# 1-Schematic.net
KiCad netlist of a schematic drawn in EasyEDA
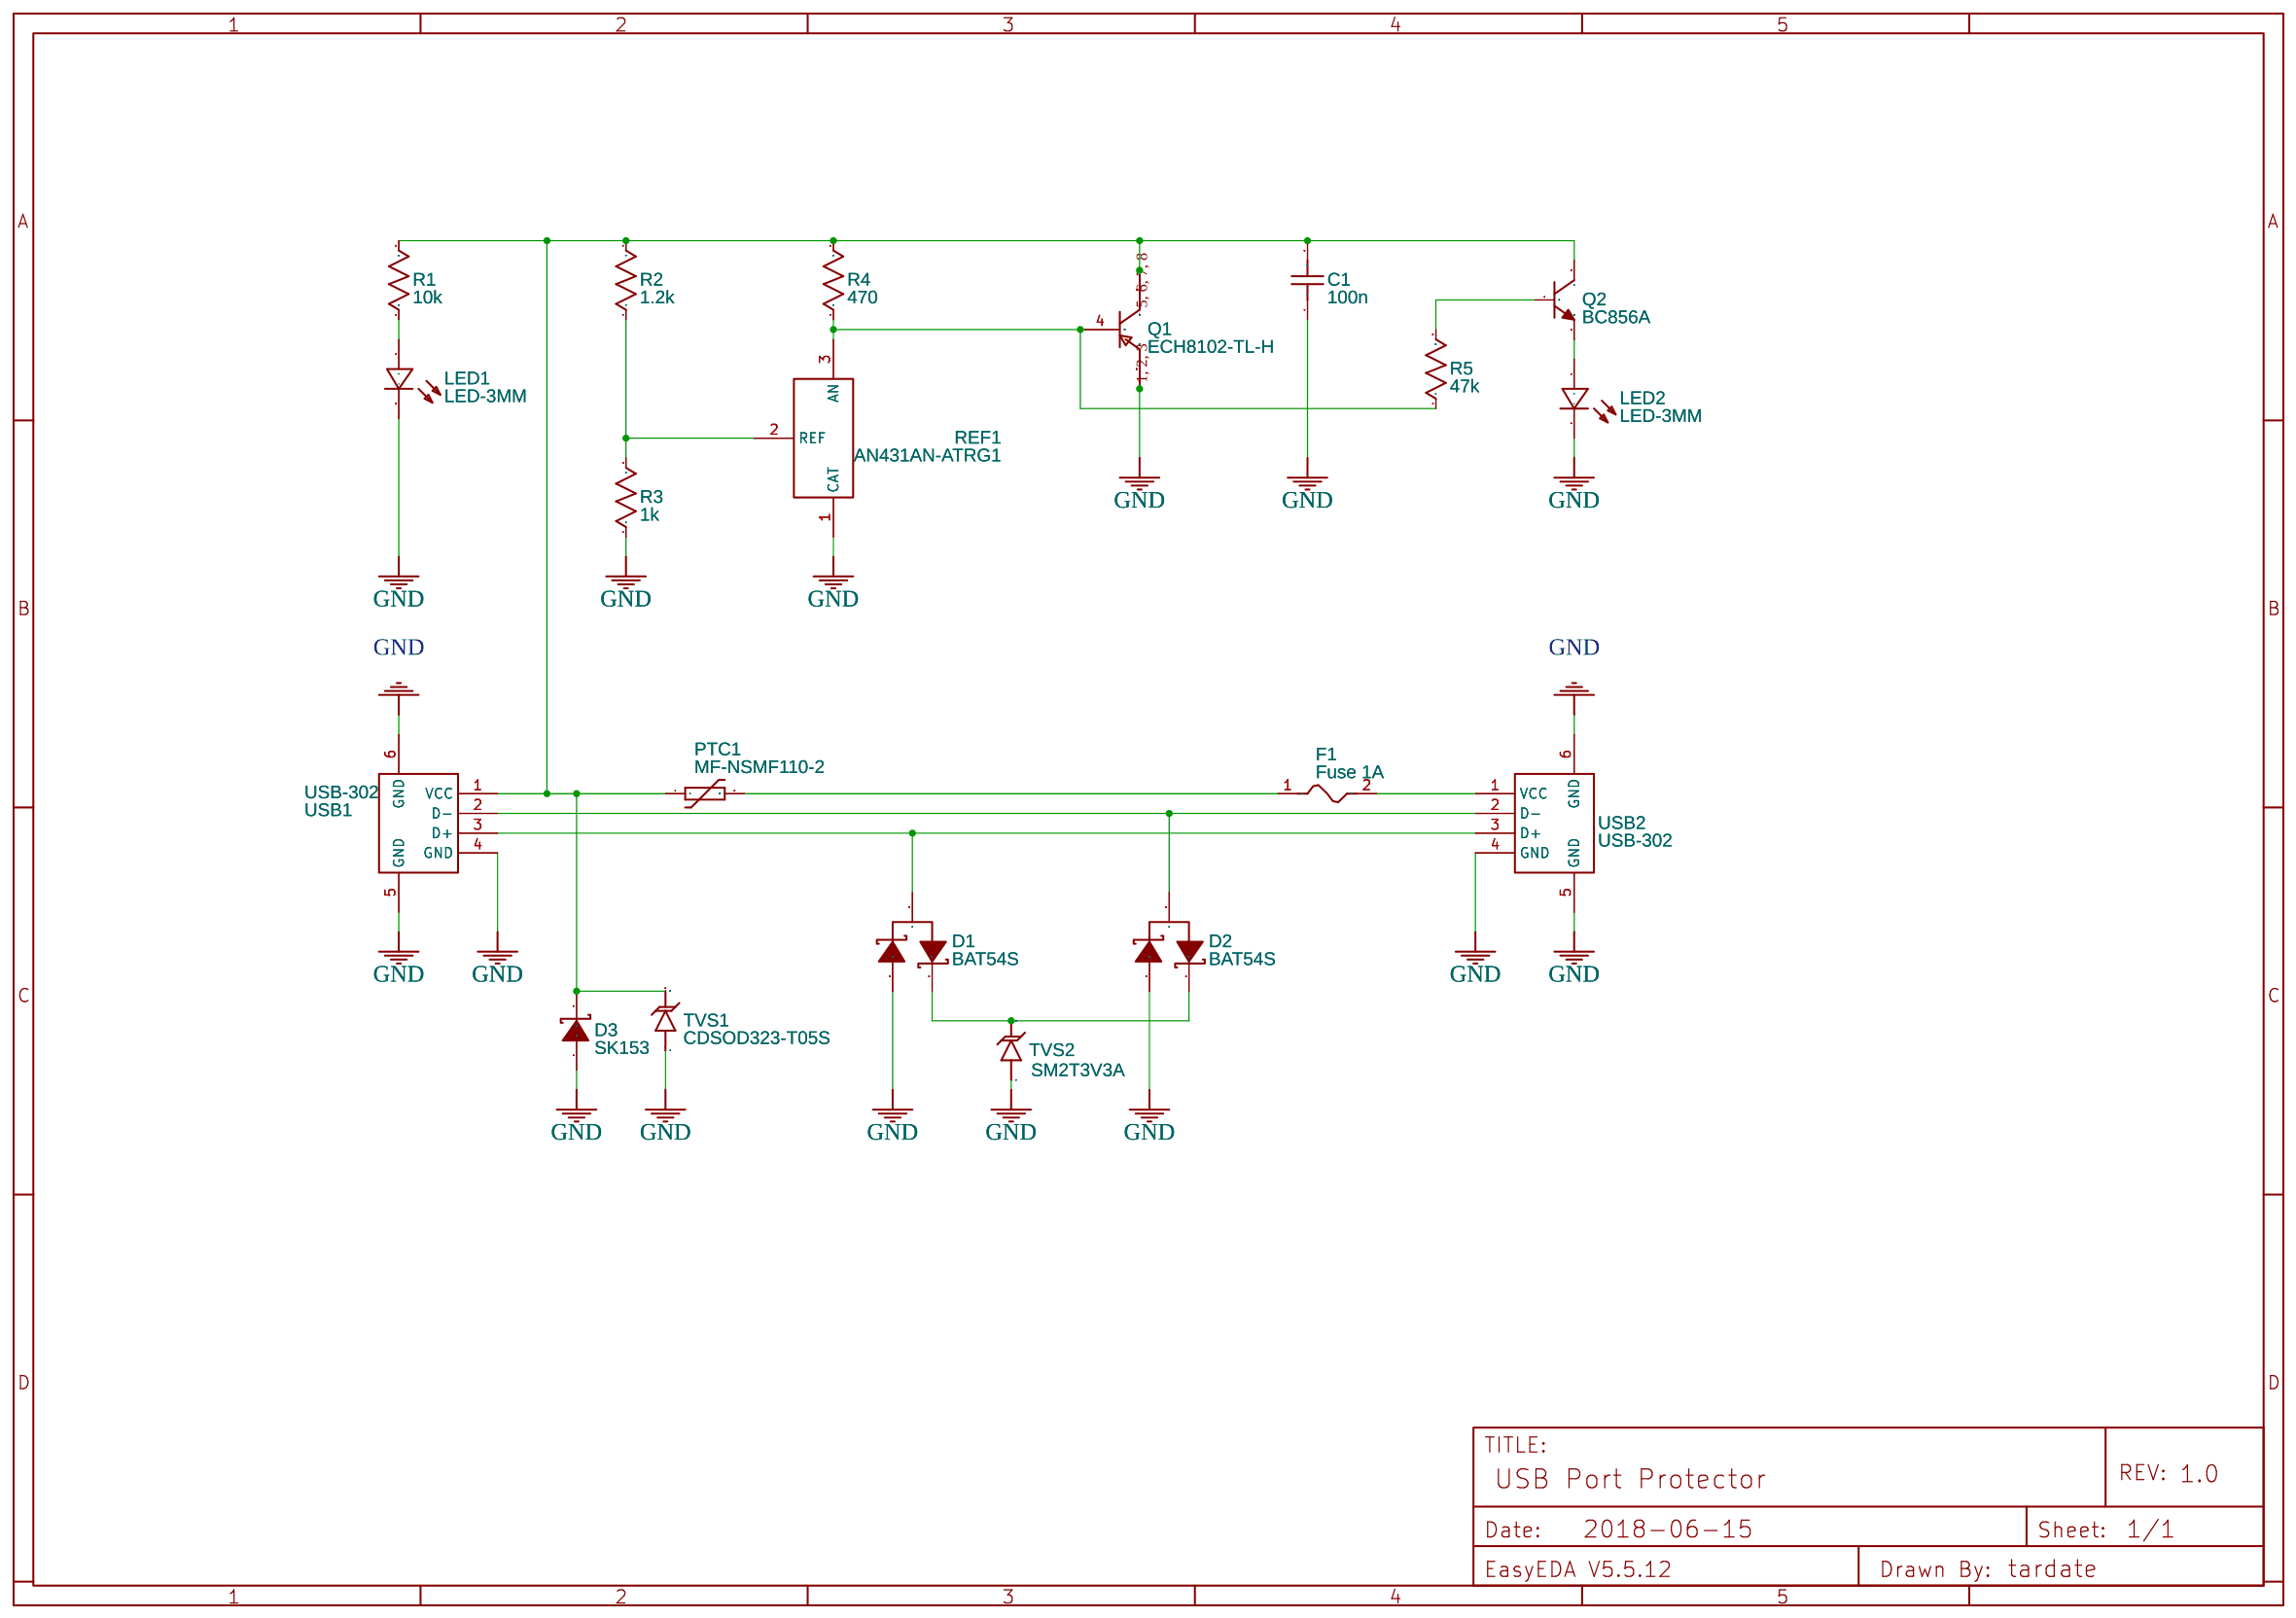
[diagram p0: schematic sheet]

(export (version "E")
  (design (tool "Eeschema 10.0.6"))
  (components
    (comp (ref "C1")
      (value "100n")
      (fields (field (name "BOM_Manufacturer Part") "?"))
      (libsource (lib "") (part "Cap_RAD-0.1_US"))
    )
    (comp (ref "D1") (value "BAT54S") (libsource (lib "") (part "Unknown_455_465")))
    (comp (ref "D2") (value "BAT54S") (libsource (lib "") (part "Unknown_585_465")))
    (comp (ref "D3")
      (value "SK153")
      (fields (field (name "BOM_Manufacturer Part") "?"))
      (libsource (lib "") (part "Schottky"))
    )
    (comp (ref "F1")
      (value "Fuse 1A")
      (fields (field (name "BOM_Manufacturer Part") "MF-NSMF110-2"))
      (libsource (lib "") (part "Unknown_670_395"))
    )
    (comp (ref "LED1")
      (value "LED-3MM")
      (fields (field (name "BOM_Manufacturer Part") "204-10UYC/S530-A3"))
      (libsource (lib "") (part "Unknown_195_185"))
    )
    (comp (ref "LED2")
      (value "LED-3MM")
      (fields (field (name "BOM_Manufacturer Part") "204-10UYC/S530-A3"))
      (libsource (lib "") (part "Unknown_790_195"))
    )
    (comp (ref "PTC1")
      (value "MF-NSMF110-2")
      (fields (field (name "BOM_Manufacturer Part") "?"))
      (libsource (lib "") (part "Unknown_350_395"))
    )
    (comp (ref "Q1")
      (value "ECH8102-TL-H")
      (fields (field (name "BOM_Manufacturer Part") "?"))
      (libsource (lib "") (part "Unknown_560_160"))
    )
    (comp (ref "Q2") (value "BC856A") (libsource (lib "") (part "Unknown_790_145")))
    (comp (ref "R1")
      (value "10k")
      (fields (field (name "BOM_Manufacturer Part") "?"))
      (libsource (lib "") (part "Res_AXIAL-0.3(1/8W)_US"))
    )
    (comp (ref "R2")
      (value "1.2k")
      (fields (field (name "BOM_Manufacturer Part") "?"))
      (libsource (lib "") (part "Res_AXIAL-0.3(1/8W)_US"))
    )
    (comp (ref "R3")
      (value "1k")
      (fields (field (name "BOM_Manufacturer Part") "?"))
      (libsource (lib "") (part "Res_AXIAL-0.3(1/8W)_US"))
    )
    (comp (ref "R4")
      (value "470")
      (fields (field (name "BOM_Manufacturer Part") "?"))
      (libsource (lib "") (part "Res_AXIAL-0.3(1/8W)_US"))
    )
    (comp (ref "R5")
      (value "47k")
      (fields (field (name "BOM_Manufacturer Part") "?"))
      (libsource (lib "") (part "Res_AXIAL-0.3(1/8W)_US"))
    )
    (comp (ref "REF1") (value "AN431AN-ATRG1") (libsource (lib "") (part "Unknown_405_215")))
    (comp (ref "TVS1")
      (value "CDSOD323-T05S")
      (fields (field (name "BOM_Manufacturer Part") "?"))
      (libsource (lib "") (part "Unknown_330_515"))
    )
    (comp (ref "TVS2")
      (value "SM2T3V3A")
      (fields (field (name "BOM_Manufacturer Part") "?"))
      (libsource (lib "") (part "Unknown_505_530"))
    )
    (comp (ref "USB1") (value "USB-302") (libsource (lib "") (part "Unknown_205_415")))
    (comp (ref "USB2") (value "USB-302") (libsource (lib "") (part "Unknown_780_415")))
  )
  (nets
    (net (code "1") (name "GND") (class "Default")
      (node (ref "C1") (pin "1") (pinfunction "1_1") (pintype "unspecified"))
      (node (ref "D1") (pin "1") (pinfunction "A1_1") (pintype "unspecified"))
      (node (ref "D2") (pin "1") (pinfunction "A1_1") (pintype "unspecified"))
      (node (ref "D3") (pin "1") (pinfunction "A_1") (pintype "unspecified"))
      (node (ref "LED1") (pin "2") (pinfunction "-_2") (pintype "unspecified"))
      (node (ref "LED2") (pin "2") (pinfunction "-_2") (pintype "unspecified"))
      (node (ref "Q1") (pin "1") (pinfunction "E_1") (pintype "unspecified"))
      (node (ref "Q1") (pin "2") (pinfunction "E_2") (pintype "unspecified"))
      (node (ref "Q1") (pin "3") (pinfunction "E_3") (pintype "unspecified"))
      (node (ref "R3") (pin "1") (pinfunction "1_1") (pintype "unspecified"))
      (node (ref "REF1") (pin "1") (pinfunction "CAT_1") (pintype "unspecified"))
      (node (ref "TVS1") (pin "A") (pinfunction "A_A") (pintype "unspecified"))
      (node (ref "TVS2") (pin "A") (pinfunction "A_A") (pintype "unspecified"))
      (node (ref "USB1") (pin "4") (pinfunction "GND_4") (pintype "unspecified"))
      (node (ref "USB1") (pin "5") (pinfunction "GND_5") (pintype "unspecified"))
      (node (ref "USB1") (pin "6") (pinfunction "GND_6") (pintype "unspecified"))
      (node (ref "USB2") (pin "4") (pinfunction "GND_4") (pintype "unspecified"))
      (node (ref "USB2") (pin "5") (pinfunction "GND_5") (pintype "unspecified"))
      (node (ref "USB2") (pin "6") (pinfunction "GND_6") (pintype "unspecified"))
    )
    (net (code "2") (name "Net-(D1-A)") (class "Default")
      (node (ref "D1") (pin "3") (pinfunction "A_3") (pintype "unspecified"))
      (node (ref "USB1") (pin "3") (pinfunction "D+_3") (pintype "unspecified"))
      (node (ref "USB2") (pin "3") (pinfunction "D+_3") (pintype "unspecified"))
    )
    (net (code "3") (name "Net-(D1-K2)") (class "Default")
      (node (ref "D1") (pin "2") (pinfunction "K2_2") (pintype "unspecified"))
      (node (ref "D2") (pin "2") (pinfunction "K2_2") (pintype "unspecified"))
      (node (ref "TVS2") (pin "C") (pinfunction "C_C") (pintype "unspecified"))
    )
    (net (code "4") (name "Net-(D2-A)") (class "Default")
      (node (ref "D2") (pin "3") (pinfunction "A_3") (pintype "unspecified"))
      (node (ref "USB1") (pin "2") (pinfunction "D-_2") (pintype "unspecified"))
      (node (ref "USB2") (pin "2") (pinfunction "D-_2") (pintype "unspecified"))
    )
    (net (code "5") (name "Net-(D3-K)") (class "Default")
      (node (ref "C1") (pin "2") (pinfunction "2_2") (pintype "unspecified"))
      (node (ref "D3") (pin "2") (pinfunction "K_2") (pintype "unspecified"))
      (node (ref "PTC1") (pin "1") (pinfunction "1_1") (pintype "unspecified"))
      (node (ref "Q1") (pin "5") (pinfunction "C_5") (pintype "unspecified"))
      (node (ref "Q1") (pin "6") (pinfunction "C_6") (pintype "unspecified"))
      (node (ref "Q1") (pin "7") (pinfunction "C_7") (pintype "unspecified"))
      (node (ref "Q1") (pin "8") (pinfunction "C_8") (pintype "unspecified"))
      (node (ref "Q2") (pin "2") (pinfunction "E_2") (pintype "unspecified"))
      (node (ref "R1") (pin "2") (pinfunction "2_2") (pintype "unspecified"))
      (node (ref "R2") (pin "2") (pinfunction "2_2") (pintype "unspecified"))
      (node (ref "R4") (pin "2") (pinfunction "2_2") (pintype "unspecified"))
      (node (ref "TVS1") (pin "C") (pinfunction "C_C") (pintype "unspecified"))
      (node (ref "USB1") (pin "1") (pinfunction "VCC_1") (pintype "unspecified"))
    )
    (net (code "6") (name "Net-(F1-Pad1)") (class "Default")
      (node (ref "F1") (pin "1") (pinfunction "1_1") (pintype "unspecified"))
      (node (ref "PTC1") (pin "2") (pinfunction "2_2") (pintype "unspecified"))
    )
    (net (code "7") (name "Net-(LED1-+)") (class "Default")
      (node (ref "LED1") (pin "1") (pinfunction "+_1") (pintype "unspecified"))
      (node (ref "R1") (pin "1") (pinfunction "1_1") (pintype "unspecified"))
    )
    (net (code "8") (name "Net-(LED2-+)") (class "Default")
      (node (ref "LED2") (pin "1") (pinfunction "+_1") (pintype "unspecified"))
      (node (ref "Q2") (pin "3") (pinfunction "C_3") (pintype "unspecified"))
    )
    (net (code "9") (name "Net-(Q1-B)") (class "Default")
      (node (ref "Q1") (pin "4") (pinfunction "B_4") (pintype "unspecified"))
      (node (ref "R4") (pin "1") (pinfunction "1_1") (pintype "unspecified"))
      (node (ref "R5") (pin "1") (pinfunction "1_1") (pintype "unspecified"))
      (node (ref "REF1") (pin "3") (pinfunction "AN_3") (pintype "unspecified"))
    )
    (net (code "10") (name "Net-(Q2-B)") (class "Default")
      (node (ref "Q2") (pin "1") (pinfunction "B_1") (pintype "unspecified"))
      (node (ref "R5") (pin "2") (pinfunction "2_2") (pintype "unspecified"))
    )
    (net (code "11") (name "Net-(REF1-REF)") (class "Default")
      (node (ref "R2") (pin "1") (pinfunction "1_1") (pintype "unspecified"))
      (node (ref "R3") (pin "2") (pinfunction "2_2") (pintype "unspecified"))
      (node (ref "REF1") (pin "2") (pinfunction "REF_2") (pintype "unspecified"))
    )
    (net (code "12") (name "Net-(USB2-VCC)") (class "Default")
      (node (ref "F1") (pin "2") (pinfunction "2_2") (pintype "unspecified"))
      (node (ref "USB2") (pin "1") (pinfunction "VCC_1") (pintype "unspecified"))
    )
  )
)
